# Sheet1.net
KiCad netlist of a schematic drawn in Altium Designer
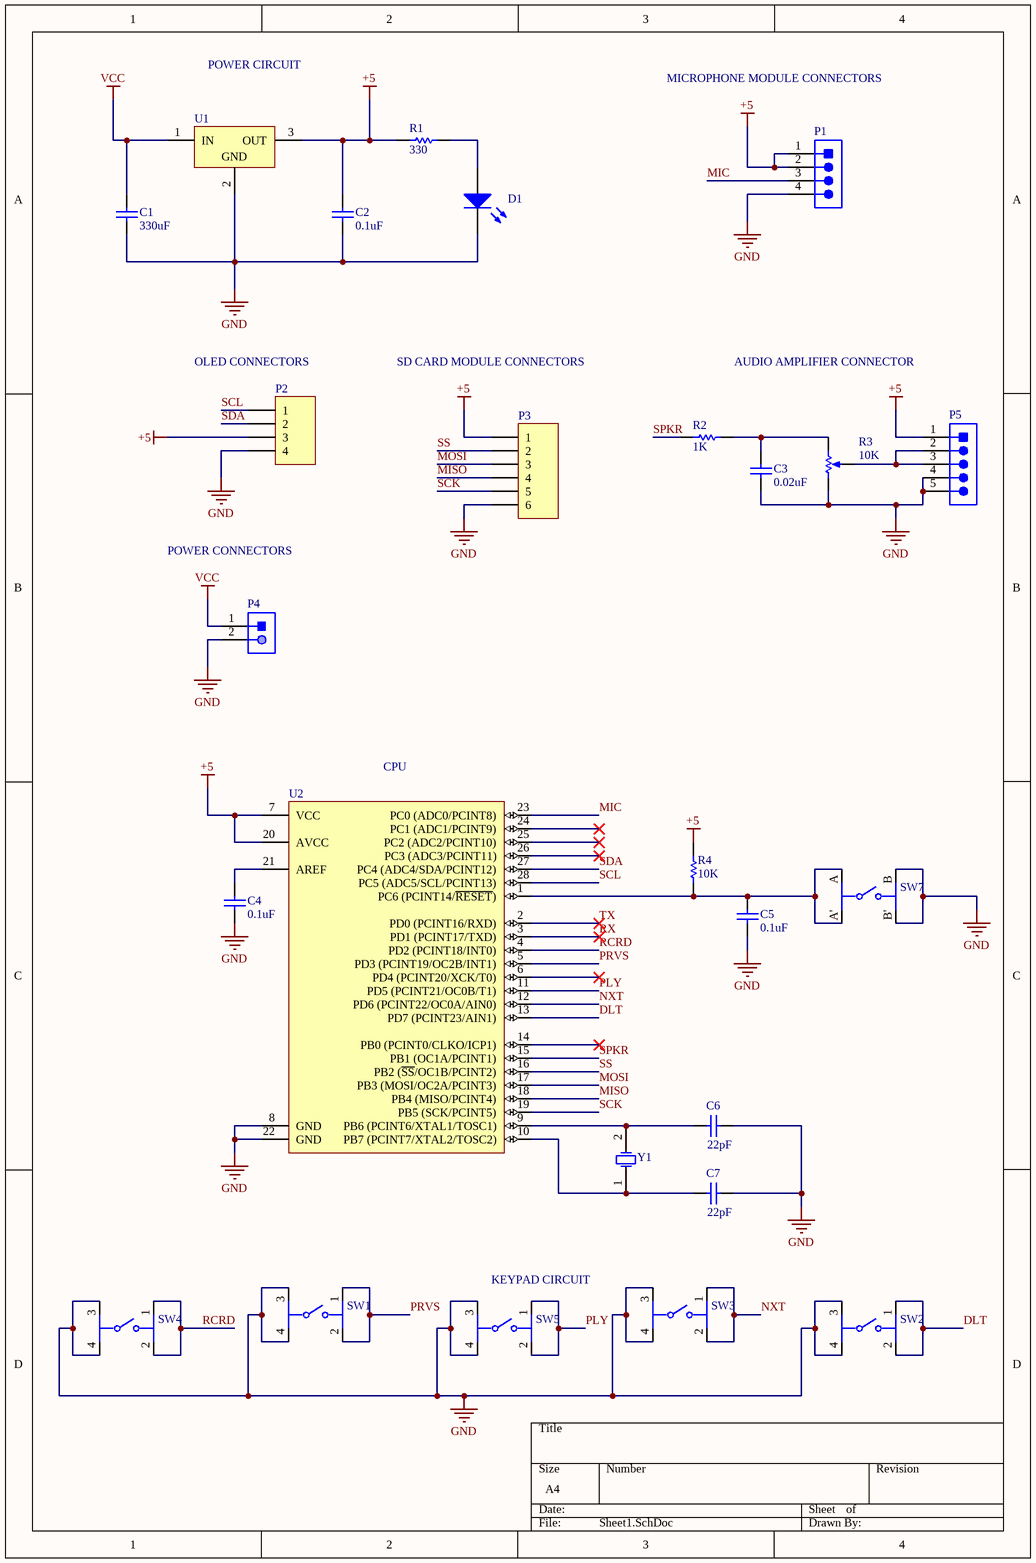
[diagram p0: Sheet1.SchDoc]

(export (version "E")
  (design (tool "Eeschema 10.0.6"))
  (components
    (comp (ref "C1")
      (value "330uF")
      (footprint "RAD-0.3")
      (description "Capacitor")
      (fields (field (name "PUBLISHER") "Altium Limited"))
      (libsource (lib "Miscellaneous Devices") (part "Cap"))
    )
    (comp (ref "C2")
      (value "0.1uF")
      (footprint "RAD-0.3")
      (description "Capacitor")
      (fields (field (name "PUBLISHER") "Altium Limited"))
      (libsource (lib "Miscellaneous Devices") (part "Cap"))
    )
    (comp (ref "C3")
      (value "0.02uF")
      (footprint "RAD-0.3")
      (description "Capacitor")
      (fields (field (name "PUBLISHER") "Altium Limited"))
      (libsource (lib "Miscellaneous Devices") (part "Cap"))
    )
    (comp (ref "C4")
      (value "~")
      (footprint "KEMT-C330C105M5U5TA")
      (description "Ceramic Capacitor, 1 uF, +/- 20%, 50 V, -10 to 85 degC, 2-Pin THD, RoHS, Bulk")
      (fields
        (field (name "TOLERANCE") "±20%")
        (field (name "CAPACITANCE") "0.1uF")
        (field (name "MANUFACTURER") "Kemet")
      )
      (libsource (lib "Altium Content Vault") (part "CAP-NP-2"))
    )
    (comp (ref "C5")
      (value "C330C105M5U5TA")
      (footprint "KEMT-C330C105M5U5TA")
      (description "Ceramic Capacitor, 1 uF, +/- 20%, 50 V, -10 to 85 degC, 2-Pin THD, RoHS, Bulk")
      (fields
        (field (name "TOLERANCE") "±20%")
        (field (name "CAPACITANCE") "0.1uF")
        (field (name "MANUFACTURER") "Kemet")
      )
      (libsource (lib "Altium Content Vault") (part "CAP-NP-2"))
    )
    (comp (ref "C6")
      (value "C330C105M5U5TA")
      (footprint "KEMT-C330C105M5U5TA")
      (description "Ceramic Capacitor, 1 uF, +/- 20%, 50 V, -10 to 85 degC, 2-Pin THD, RoHS, Bulk")
      (fields
        (field (name "TOLERANCE") "±20%")
        (field (name "CAPACITANCE") "22pF")
        (field (name "MANUFACTURER") "Kemet")
      )
      (libsource (lib "Altium Content Vault") (part "CAP-NP-2"))
    )
    (comp (ref "C7")
      (value "C330C105M5U5TA")
      (footprint "KEMT-C330C105M5U5TA")
      (description "Ceramic Capacitor, 1 uF, +/- 20%, 50 V, -10 to 85 degC, 2-Pin THD, RoHS, Bulk")
      (fields
        (field (name "TOLERANCE") "±20%")
        (field (name "CAPACITANCE") "22pF")
        (field (name "MANUFACTURER") "Kemet")
      )
      (libsource (lib "Altium Content Vault") (part "CAP-NP-2"))
    )
    (comp (ref "D1")
      (value "LED1")
      (footprint "LED-1")
      (description "Typical RED GaAs LED")
      (fields (field (name "PUBLISHER") "Altium Limited"))
      (libsource (lib "Miscellaneous Devices") (part "LED1"))
    )
    (comp (ref "P1")
      (value "640456-4")
      (footprint "TECO-640456-4")
      (description "Male Header, Pitch 2.54 mm, 1 x 4 Position, Height 10.03 mm, Tail Length 3.56 mm, RoHS, Bulk")
      (fields (field (name "MANUFACTURER") "TE Connectivity"))
      (libsource (lib "Altium Content Vault") (part "CN-1P-M-R4"))
    )
    (comp (ref "P2")
      (value "Header 4")
      (footprint "HDR1X4")
      (description "Header, 4-Pin")
      (fields (field (name "PUBLISHER") "Altium Limited"))
      (libsource (lib "Miscellaneous Connectors") (part "Header 4"))
    )
    (comp (ref "P3")
      (value "Header 6")
      (footprint "HDR1X6")
      (description "Header, 6-Pin")
      (fields (field (name "PUBLISHER") "Altium Limited"))
      (libsource (lib "Miscellaneous Connectors") (part "Header 6"))
    )
    (comp (ref "P4")
      (value "61900211121")
      (footprint "61900211121")
      (description "Male Locking Header WR-WTB, THT, Vertical, pitch 2.54 mm, 1 x 2 position")
      (fields (field (name "MANUFACTURER") "Wurth Elektronik") (field (name "PUBLISHER") "WurthElektronik"))
      (libsource (lib "Altium Content Vault") (part "WE-CN-1P-M-R2"))
    )
    (comp (ref "P5")
      (value "640456-5")
      (footprint "TECO-640456-5")
      (fields (field (name "MANUFACTURER") "TE Connectivity"))
      (libsource (lib "Altium Content Vault") (part "CN-1P-M-R5"))
    )
    (comp (ref "R1")
      (value "330")
      (footprint "AXIAL-0.3")
      (description "Resistor")
      (fields (field (name "PUBLISHER") "Altium Limited"))
      (libsource (lib "Miscellaneous Devices") (part "Res1"))
    )
    (comp (ref "R2")
      (value "1K")
      (footprint "AXIAL-0.3")
      (description "Resistor")
      (fields (field (name "PUBLISHER") "Altium Limited"))
      (libsource (lib "Miscellaneous Devices") (part "Res1"))
    )
    (comp (ref "R3")
      (value "10K")
      (footprint "VR5")
      (description "Potentiometer")
      (fields (field (name "PUBLISHER") "Altium Limited"))
      (libsource (lib "Miscellaneous Devices") (part "RPot"))
    )
    (comp (ref "R4")
      (value "10K")
      (footprint "AXIAL-0.3")
      (description "Resistor")
      (fields (field (name "PUBLISHER") "Altium Limited"))
      (libsource (lib "Miscellaneous Devices") (part "Res1"))
    )
    (comp (ref "SW1")
      (value "FSM100")
      (footprint "FP-FSM100-MFG")
      (description "SWITCH TACTILE SPST-NO 0.05A 24V")
      (libsource (lib "Altium Content Vault") (part "1adf0dd01260c80cf25a44bfd6b99ba"))
    )
    (comp (ref "SW2")
      (value "FSM100")
      (footprint "FP-FSM100-MFG")
      (description "SWITCH TACTILE SPST-NO 0.05A 24V")
      (libsource (lib "Altium Content Vault") (part "1adf0dd01260c80cf25a44bfd6b99ba"))
    )
    (comp (ref "SW3")
      (value "FSM100")
      (footprint "FP-FSM100-MFG")
      (description "SWITCH TACTILE SPST-NO 0.05A 24V")
      (libsource (lib "Altium Content Vault") (part "1adf0dd01260c80cf25a44bfd6b99ba"))
    )
    (comp (ref "SW4")
      (value "FSM100")
      (footprint "FP-FSM100-MFG")
      (description "SWITCH TACTILE SPST-NO 0.05A 24V")
      (libsource (lib "Altium Content Vault") (part "1adf0dd01260c80cf25a44bfd6b99ba"))
    )
    (comp (ref "SW5")
      (value "FSM100")
      (footprint "FP-FSM100-MFG")
      (description "SWITCH TACTILE SPST-NO 0.05A 24V")
      (libsource (lib "Altium Content Vault") (part "1adf0dd01260c80cf25a44bfd6b99ba"))
    )
    (comp (ref "SW7")
      (value "EVQ-PAG07K")
      (footprint "FP-EVQ-PAG07K-MFG")
      (description "SWITCH TACTILE SPST-NO 0.02A 15V")
      (libsource (lib "Altium Content Vault") (part "75038bc65b1af1a6bd057da08483287"))
    )
    (comp (ref "U1")
      (value "L7805CV")
      (footprint "TO220")
      (description "Positive Voltage Regulator, 5V, 3-Pin TO-220")
      (libsource (lib "Altium Content Vault") (part "PM-REG-L4940-SIL3"))
    )
    (comp (ref "U2")
      (value "ATmega328P-PU")
      (footprint "28P3")
      (libsource (lib "Altium Content Vault") (part "MC-8B-ATM48-IL28"))
    )
    (comp (ref "Y1")
      (value "XTAL")
      (footprint "R38")
      (description "Crystal Oscillator")
      (fields (field (name "PUBLISHER") "Altium Limited"))
      (libsource (lib "Miscellaneous Devices") (part "XTAL"))
    )
  )
  (nets
    (net (code "1") (name "+5") (class "Default")
      (node (ref "C2") (pin "2") (pinfunction "2_2") (pintype "passive"))
      (node (ref "P1") (pin "1") (pinfunction "1_1") (pintype "passive"))
      (node (ref "P1") (pin "2") (pinfunction "2_2") (pintype "passive"))
      (node (ref "P2") (pin "3") (pinfunction "3_3") (pintype "passive"))
      (node (ref "P3") (pin "1") (pinfunction "1_1") (pintype "passive"))
      (node (ref "P5") (pin "1") (pinfunction "DTR_1") (pintype "passive"))
      (node (ref "R1") (pin "1") (pinfunction "1_1") (pintype "passive"))
      (node (ref "R4") (pin "1") (pinfunction "1_1") (pintype "passive"))
      (node (ref "U1") (pin "3") (pinfunction "OUT_3") (pintype "power_in"))
      (node (ref "U2") (pin "20") (pinfunction "AVCC_20") (pintype "power_in"))
      (node (ref "U2") (pin "7") (pinfunction "VCC_7") (pintype "power_in"))
    )
    (net (code "2") (name "/DLT") (class "Default")
      (node (ref "SW2") (pin "1") (pinfunction "1_1") (pintype "passive"))
      (node (ref "SW2") (pin "2") (pinfunction "2_2") (pintype "passive"))
      (node (ref "U2") (pin "13") (pinfunction "PD7_(PCINT23/AIN1)_13") (pintype "bidirectional"))
    )
    (net (code "3") (name "/MIC") (class "Default")
      (node (ref "P1") (pin "3") (pinfunction "3_3") (pintype "passive"))
      (node (ref "U2") (pin "23") (pinfunction "PC0_(ADC0/PCINT8)_23") (pintype "bidirectional"))
    )
    (net (code "4") (name "/MISO") (class "Default")
      (node (ref "P3") (pin "4") (pinfunction "4_4") (pintype "passive"))
      (node (ref "U2") (pin "18") (pinfunction "PB4_(MISO/PCINT4)_18") (pintype "bidirectional"))
    )
    (net (code "5") (name "/MOSI") (class "Default")
      (node (ref "P3") (pin "3") (pinfunction "3_3") (pintype "passive"))
      (node (ref "U2") (pin "17") (pinfunction "PB3_(MOSI/OC2A/PCINT3)_17") (pintype "bidirectional"))
    )
    (net (code "6") (name "/NXT") (class "Default")
      (node (ref "SW3") (pin "1") (pinfunction "1_1") (pintype "passive"))
      (node (ref "SW3") (pin "2") (pinfunction "2_2") (pintype "passive"))
      (node (ref "U2") (pin "12") (pinfunction "PD6_(PCINT22/OC0A/AIN0)_12") (pintype "bidirectional"))
    )
    (net (code "7") (name "/PLY") (class "Default")
      (node (ref "SW5") (pin "1") (pinfunction "1_1") (pintype "passive"))
      (node (ref "SW5") (pin "2") (pinfunction "2_2") (pintype "passive"))
      (node (ref "U2") (pin "11") (pinfunction "PD5_(PCINT21/OC0B/T1)_11") (pintype "bidirectional"))
    )
    (net (code "8") (name "/PRVS") (class "Default")
      (node (ref "SW1") (pin "1") (pinfunction "1_1") (pintype "passive"))
      (node (ref "SW1") (pin "2") (pinfunction "2_2") (pintype "passive"))
      (node (ref "U2") (pin "5") (pinfunction "PD3_(PCINT19/OC2B/INT1)_5") (pintype "bidirectional"))
    )
    (net (code "9") (name "/RCRD") (class "Default")
      (node (ref "SW4") (pin "1") (pinfunction "1_1") (pintype "passive"))
      (node (ref "SW4") (pin "2") (pinfunction "2_2") (pintype "passive"))
      (node (ref "U2") (pin "4") (pinfunction "PD2_(PCINT18/INT0)_4") (pintype "bidirectional"))
    )
    (net (code "10") (name "/RX") (class "Default")
      (node (ref "U2") (pin "3") (pinfunction "PD1_(PCINT17/TXD)_3") (pintype "bidirectional+no_connect"))
    )
    (net (code "11") (name "/SCK") (class "Default")
      (node (ref "P3") (pin "5") (pinfunction "5_5") (pintype "passive"))
      (node (ref "U2") (pin "19") (pinfunction "PB5_(SCK/PCINT5)_19") (pintype "bidirectional"))
    )
    (net (code "12") (name "/SCL") (class "Default")
      (node (ref "P2") (pin "1") (pinfunction "1_1") (pintype "passive"))
      (node (ref "U2") (pin "28") (pinfunction "PC5_(ADC5/SCL/PCINT13)_28") (pintype "bidirectional"))
    )
    (net (code "13") (name "/SDA") (class "Default")
      (node (ref "P2") (pin "2") (pinfunction "2_2") (pintype "passive"))
      (node (ref "U2") (pin "27") (pinfunction "PC4_(ADC4/SDA/PCINT12)_27") (pintype "bidirectional"))
    )
    (net (code "14") (name "/SPKR") (class "Default")
      (node (ref "R2") (pin "2") (pinfunction "2_2") (pintype "passive"))
      (node (ref "U2") (pin "15") (pinfunction "PB1_(OC1A/PCINT1)_15") (pintype "bidirectional"))
    )
    (net (code "15") (name "/SS") (class "Default")
      (node (ref "P3") (pin "2") (pinfunction "2_2") (pintype "passive"))
      (node (ref "U2") (pin "16") (pinfunction "PB2_(~{SS}/OC1B/PCINT2)_16") (pintype "bidirectional"))
    )
    (net (code "16") (name "/TX") (class "Default")
      (node (ref "U2") (pin "2") (pinfunction "PD0_(PCINT16/RXD)_2") (pintype "bidirectional+no_connect"))
    )
    (net (code "17") (name "GND") (class "Default")
      (node (ref "C1") (pin "1") (pinfunction "1_1") (pintype "passive"))
      (node (ref "C2") (pin "1") (pinfunction "1_1") (pintype "passive"))
      (node (ref "C3") (pin "1") (pinfunction "1_1") (pintype "passive"))
      (node (ref "C4") (pin "1") (pinfunction "1_1") (pintype "passive"))
      (node (ref "C5") (pin "1") (pinfunction "1_1") (pintype "passive"))
      (node (ref "C6") (pin "2") (pinfunction "2_2") (pintype "passive"))
      (node (ref "C7") (pin "2") (pinfunction "2_2") (pintype "passive"))
      (node (ref "D1") (pin "2") (pinfunction "K_2") (pintype "passive"))
      (node (ref "P1") (pin "4") (pinfunction "4_4") (pintype "passive"))
      (node (ref "P2") (pin "4") (pinfunction "4_4") (pintype "passive"))
      (node (ref "P3") (pin "6") (pinfunction "6_6") (pintype "passive"))
      (node (ref "P4") (pin "2") (pinfunction "2_2") (pintype "passive"))
      (node (ref "P5") (pin "4") (pinfunction "VCC_4") (pintype "passive"))
      (node (ref "P5") (pin "5") (pinfunction "CTS_5") (pintype "passive"))
      (node (ref "R3") (pin "1") (pinfunction "TOP_1") (pintype "passive"))
      (node (ref "SW1") (pin "3") (pinfunction "3_3") (pintype "passive"))
      (node (ref "SW1") (pin "4") (pinfunction "4_4") (pintype "passive"))
      (node (ref "SW2") (pin "3") (pinfunction "3_3") (pintype "passive"))
      (node (ref "SW2") (pin "4") (pinfunction "4_4") (pintype "passive"))
      (node (ref "SW3") (pin "3") (pinfunction "3_3") (pintype "passive"))
      (node (ref "SW3") (pin "4") (pinfunction "4_4") (pintype "passive"))
      (node (ref "SW4") (pin "3") (pinfunction "3_3") (pintype "passive"))
      (node (ref "SW4") (pin "4") (pinfunction "4_4") (pintype "passive"))
      (node (ref "SW5") (pin "3") (pinfunction "3_3") (pintype "passive"))
      (node (ref "SW5") (pin "4") (pinfunction "4_4") (pintype "passive"))
      (node (ref "SW7") (pin "B") (pinfunction "B_B") (pintype "passive"))
      (node (ref "SW7") (pin "B'") (pinfunction "B'_B'") (pintype "passive"))
      (node (ref "U1") (pin "2") (pinfunction "GND_2") (pintype "power_in"))
      (node (ref "U2") (pin "22") (pinfunction "GND_22") (pintype "power_in"))
      (node (ref "U2") (pin "8") (pinfunction "GND_8") (pintype "power_in"))
    )
    (net (code "18") (name "Net-(D1-A)") (class "Default")
      (node (ref "D1") (pin "1") (pinfunction "A_1") (pintype "passive"))
      (node (ref "R1") (pin "2") (pinfunction "2_2") (pintype "passive"))
    )
    (net (code "19") (name "Net-(P5-RXI)") (class "Default")
      (node (ref "P5") (pin "2") (pinfunction "RXI_2") (pintype "passive"))
      (node (ref "P5") (pin "3") (pinfunction "TXO_3") (pintype "passive"))
      (node (ref "R3") (pin "3") (pinfunction "TAP_3") (pintype "passive"))
    )
    (net (code "20") (name "Net-(R3-BOT)") (class "Default")
      (node (ref "C3") (pin "2") (pinfunction "2_2") (pintype "passive"))
      (node (ref "R2") (pin "1") (pinfunction "1_1") (pintype "passive"))
      (node (ref "R3") (pin "2") (pinfunction "BOT_2") (pintype "passive"))
    )
    (net (code "21") (name "Net-(U2-AREF)") (class "Default")
      (node (ref "C4") (pin "2") (pinfunction "2_2") (pintype "passive"))
      (node (ref "U2") (pin "21") (pinfunction "AREF_21") (pintype "power_in"))
    )
    (net (code "22") (name "Net-(U2-PB6_(PCINT6{slash}XTAL1{slash}TOSC1))") (class "Default")
      (node (ref "C6") (pin "1") (pinfunction "1_1") (pintype "passive"))
      (node (ref "U2") (pin "9") (pinfunction "PB6_(PCINT6/XTAL1/TOSC1)_9") (pintype "bidirectional"))
      (node (ref "Y1") (pin "2") (pinfunction "OSC2_2") (pintype "passive"))
    )
    (net (code "23") (name "Net-(U2-PB7_(PCINT7{slash}XTAL2{slash}TOSC2))") (class "Default")
      (node (ref "C7") (pin "1") (pinfunction "1_1") (pintype "passive"))
      (node (ref "U2") (pin "10") (pinfunction "PB7_(PCINT7/XTAL2/TOSC2)_10") (pintype "bidirectional"))
      (node (ref "Y1") (pin "1") (pinfunction "OSC1_1") (pintype "passive"))
    )
    (net (code "24") (name "Net-(U2-PC6_(PCINT14{slash}~{RESET}))") (class "Default")
      (node (ref "C5") (pin "2") (pinfunction "2_2") (pintype "passive"))
      (node (ref "R4") (pin "2") (pinfunction "2_2") (pintype "passive"))
      (node (ref "SW7") (pin "A") (pinfunction "A_A") (pintype "passive"))
      (node (ref "SW7") (pin "A'") (pinfunction "A'_A'") (pintype "passive"))
      (node (ref "U2") (pin "1") (pinfunction "PC6_(PCINT14/~{RESET})_1") (pintype "bidirectional"))
    )
    (net (code "25") (name "VCC") (class "Default")
      (node (ref "C1") (pin "2") (pinfunction "2_2") (pintype "passive"))
      (node (ref "P4") (pin "1") (pinfunction "1_1") (pintype "passive"))
      (node (ref "U1") (pin "1") (pinfunction "IN_1") (pintype "power_in"))
    )
    (net (code "26") (name "unconnected-(U2-PB0_(PCINT0{slash}CLKO{slash}ICP1)-Pad14)") (class "Default")
      (node (ref "U2") (pin "14") (pinfunction "PB0_(PCINT0/CLKO/ICP1)_14") (pintype "bidirectional+no_connect"))
    )
    (net (code "27") (name "unconnected-(U2-PC1_(ADC1{slash}PCINT9)-Pad24)") (class "Default")
      (node (ref "U2") (pin "24") (pinfunction "PC1_(ADC1/PCINT9)_24") (pintype "bidirectional+no_connect"))
    )
    (net (code "28") (name "unconnected-(U2-PC2_(ADC2{slash}PCINT10)-Pad25)") (class "Default")
      (node (ref "U2") (pin "25") (pinfunction "PC2_(ADC2/PCINT10)_25") (pintype "bidirectional+no_connect"))
    )
    (net (code "29") (name "unconnected-(U2-PC3_(ADC3{slash}PCINT11)-Pad26)") (class "Default")
      (node (ref "U2") (pin "26") (pinfunction "PC3_(ADC3/PCINT11)_26") (pintype "bidirectional+no_connect"))
    )
    (net (code "30") (name "unconnected-(U2-PD4_(PCINT20{slash}XCK{slash}T0)-Pad6)") (class "Default")
      (node (ref "U2") (pin "6") (pinfunction "PD4_(PCINT20/XCK/T0)_6") (pintype "bidirectional+no_connect"))
    )
  )
)
